# CH32V407VET-R0.net
KiCad netlist of a schematic drawn in Altium Designer
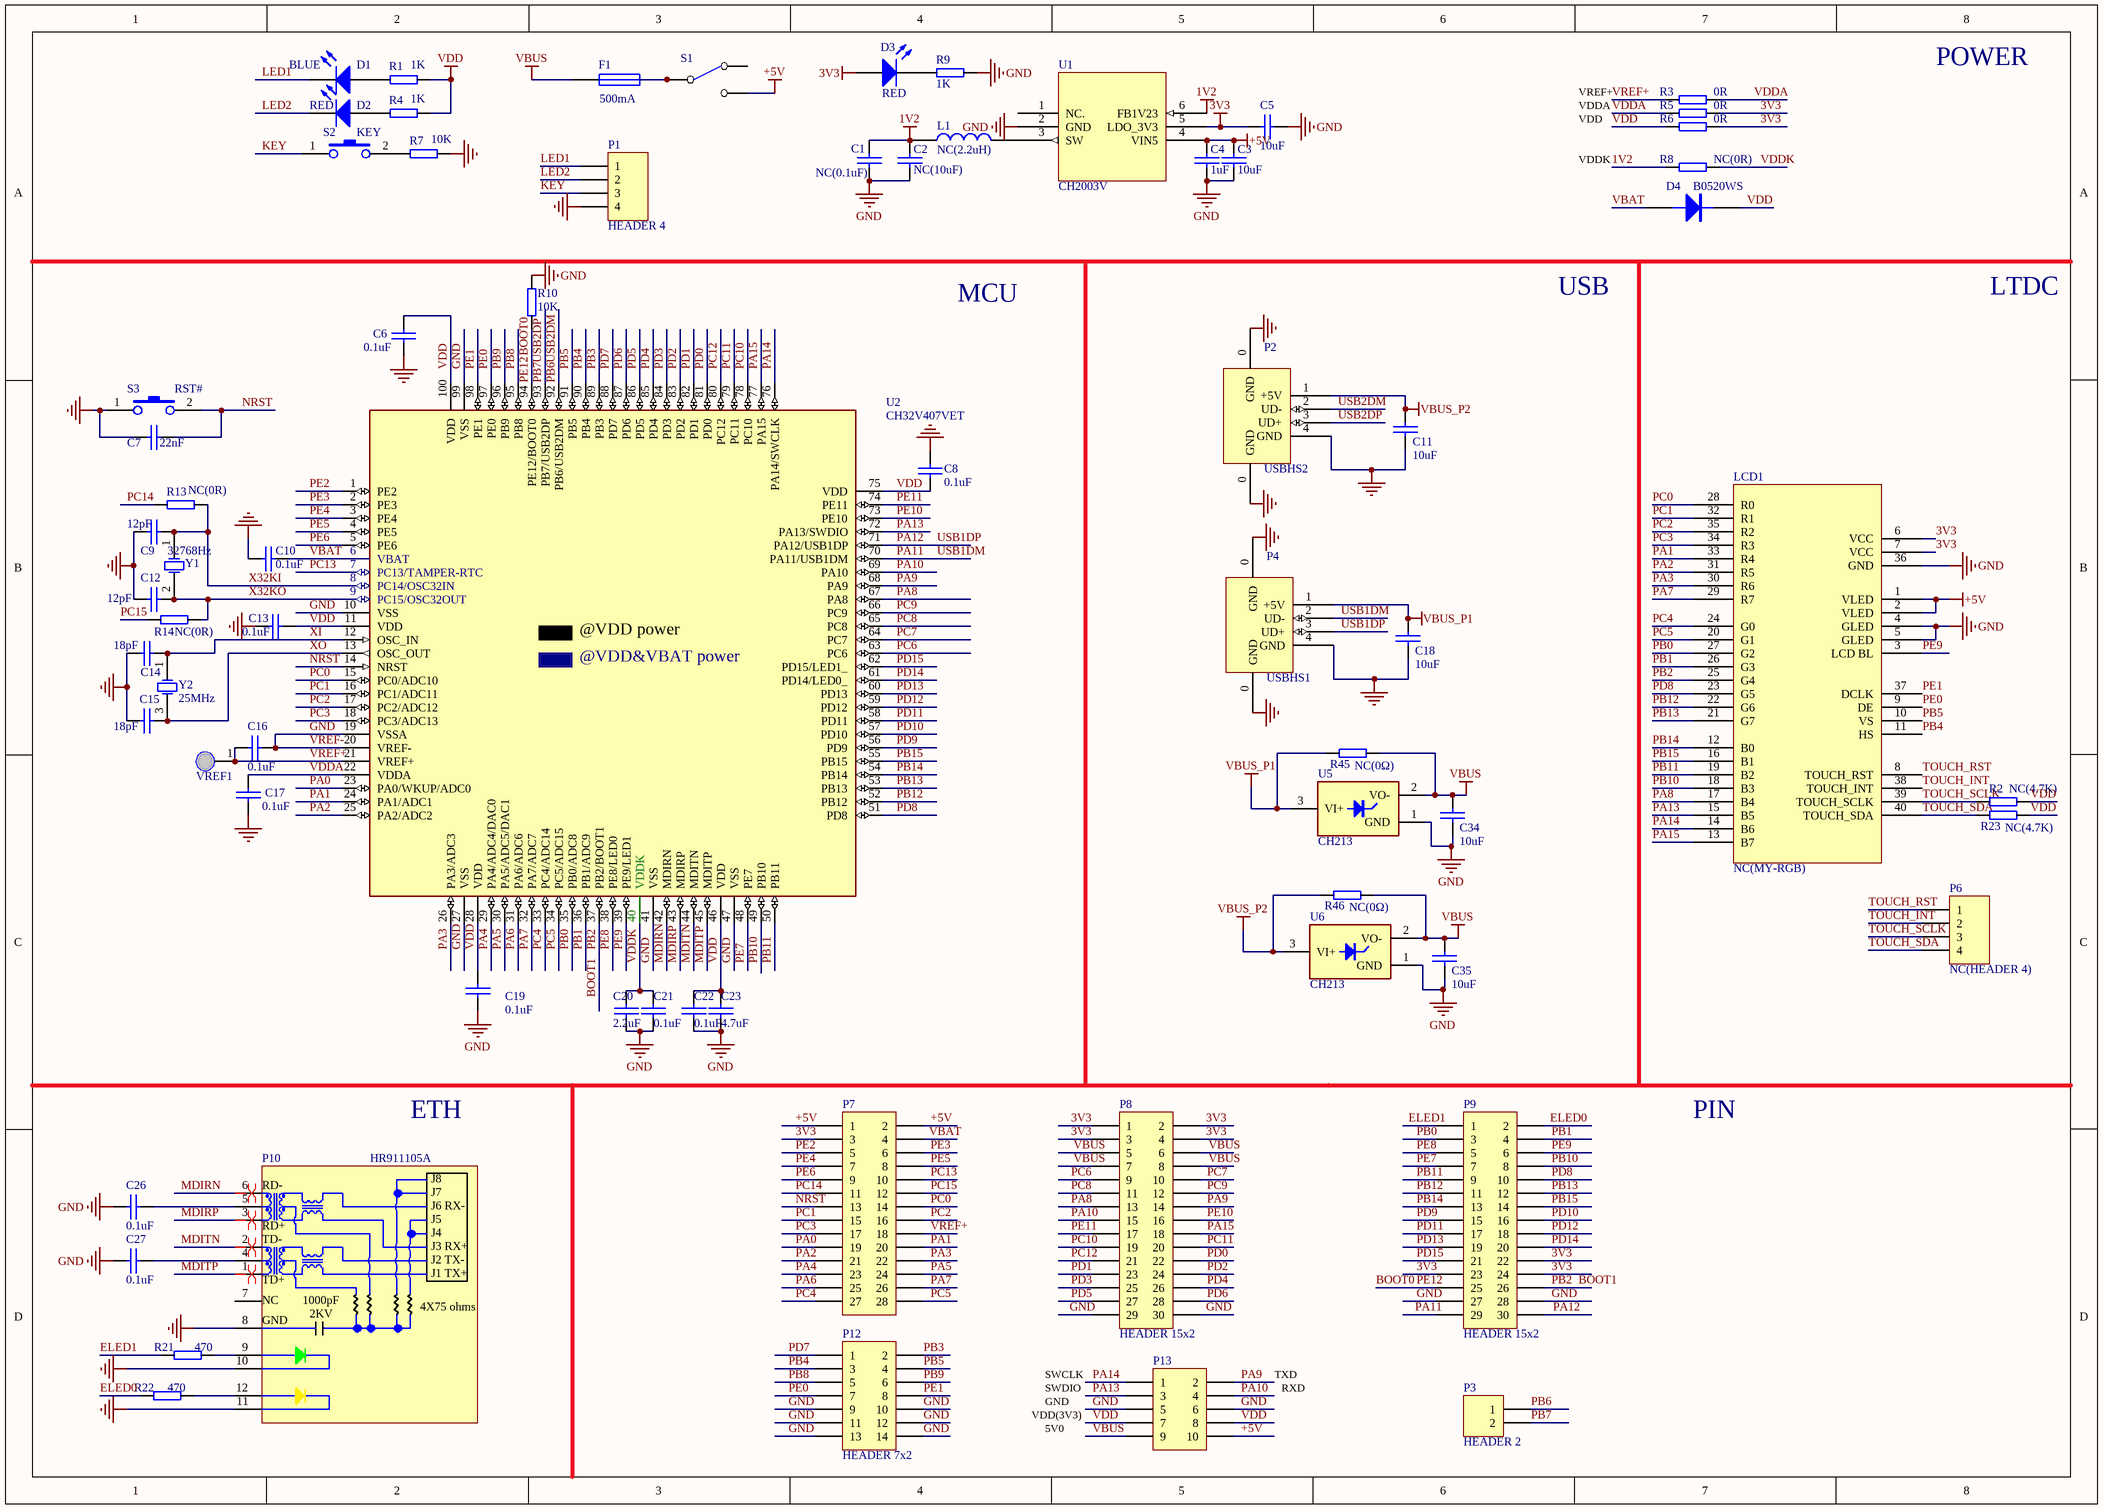
[diagram p0: CH32V407VET-R0.SchDoc]

(export (version "E")
  (design (tool "Eeschema 10.0.6"))
  (components
    (comp (ref "C1")
      (value "NC(0.1uF)")
      (footprint "0402_C")
      (description "Capacitor")
      (libsource (lib "") (part "CAP_1"))
    )
    (comp (ref "C2")
      (value "NC(10uF)")
      (footprint "0603_C")
      (description "Capacitor")
      (libsource (lib "*") (part "CAP"))
    )
    (comp (ref "C3")
      (value "10uF")
      (footprint "0603_C")
      (description "Capacitor")
      (libsource (lib "*") (part "CAP"))
    )
    (comp (ref "C4")
      (value "1uF")
      (footprint "0402_C")
      (description "Capacitor")
      (libsource (lib "") (part "CAP_1"))
    )
    (comp (ref "C5")
      (value "10uF")
      (footprint "0603_C")
      (description "Capacitor")
      (libsource (lib "*") (part "CAP"))
    )
    (comp (ref "C6")
      (value "0.1uF")
      (footprint "0402_C")
      (description "Capacitor")
      (libsource (lib "*") (part "CAP"))
    )
    (comp (ref "C7")
      (value "22nF")
      (footprint "0402_C")
      (description "Capacitor")
      (libsource (lib "") (part "CAP_2"))
    )
    (comp (ref "C8")
      (value "0.1uF")
      (footprint "0402_C")
      (description "Capacitor")
      (libsource (lib "*") (part "CAP"))
    )
    (comp (ref "C9")
      (value "12pF")
      (footprint "0402_C")
      (description "Capacitor")
      (libsource (lib "*") (part "CAP"))
    )
    (comp (ref "C10")
      (value "0.1uF")
      (footprint "0402_C")
      (description "Capacitor")
      (libsource (lib "*") (part "CAP"))
    )
    (comp (ref "C11")
      (value "10uF")
      (footprint "0603_C")
      (description "Capacitor")
      (libsource (lib "") (part "CAP_2"))
    )
    (comp (ref "C12")
      (value "12pF")
      (footprint "0402_C")
      (description "Capacitor")
      (libsource (lib "*") (part "CAP"))
    )
    (comp (ref "C13")
      (value "0.1uF")
      (footprint "0402_C")
      (description "Capacitor")
      (libsource (lib "*") (part "CAP"))
    )
    (comp (ref "C14")
      (value "18pF")
      (footprint "0402_C")
      (description "Capacitor")
      (libsource (lib "*") (part "CAP"))
    )
    (comp (ref "C15")
      (value "18pF")
      (footprint "0402_C")
      (description "Capacitor")
      (libsource (lib "*") (part "CAP"))
    )
    (comp (ref "C16")
      (value "0.1uF")
      (footprint "0402_C")
      (description "Capacitor")
      (libsource (lib "*") (part "CAP"))
    )
    (comp (ref "C17")
      (value "0.1uF")
      (footprint "0402_C")
      (description "Capacitor")
      (libsource (lib "*") (part "CAP"))
    )
    (comp (ref "C18")
      (value "10uF")
      (footprint "0603_C")
      (description "Capacitor")
      (libsource (lib "") (part "CAP_2"))
    )
    (comp (ref "C19")
      (value "0.1uF")
      (footprint "0402_C")
      (description "Capacitor")
      (libsource (lib "*") (part "CAP"))
    )
    (comp (ref "C20")
      (value "2.2uF")
      (footprint "0402_C")
      (description "Capacitor")
      (libsource (lib "*") (part "CAP"))
    )
    (comp (ref "C21")
      (value "0.1uF")
      (footprint "0402_C")
      (description "Capacitor")
      (libsource (lib "*") (part "CAP"))
    )
    (comp (ref "C22")
      (value "0.1uF")
      (footprint "0402_C")
      (description "Capacitor")
      (libsource (lib "*") (part "CAP"))
    )
    (comp (ref "C23")
      (value "4.7uF")
      (footprint "0402_C")
      (description "Capacitor")
      (libsource (lib "*") (part "CAP"))
    )
    (comp (ref "C26")
      (value "0.1uF")
      (footprint "0402_C")
      (description "Capacitor")
      (libsource (lib "wch_sch_others") (part "CAP"))
    )
    (comp (ref "C27")
      (value "0.1uF")
      (footprint "0402_C")
      (description "Capacitor")
      (libsource (lib "wch_sch_others") (part "CAP"))
    )
    (comp (ref "C34")
      (value "10uF")
      (footprint "0603_C")
      (description "Capacitor")
      (libsource (lib "") (part "CAP_2"))
    )
    (comp (ref "C35")
      (value "10uF")
      (footprint "0603_C")
      (description "Capacitor")
      (libsource (lib "") (part "CAP_2"))
    )
    (comp (ref "D1")
      (value "BLUE")
      (footprint "0603+")
      (description "Typical INFRARED GaAs LED")
      (fields (field (name "PUBLISHER") "Altium Limited"))
      (libsource (lib "*") (part "LED0"))
    )
    (comp (ref "D2")
      (value "RED")
      (footprint "0603+")
      (description "Typical INFRARED GaAs LED")
      (fields (field (name "PUBLISHER") "Altium Limited"))
      (libsource (lib "*") (part "LED0"))
    )
    (comp (ref "D3")
      (value "RED")
      (footprint "0603+")
      (description "Typical INFRARED GaAs LED")
      (fields (field (name "PUBLISHER") "Altium Limited"))
      (libsource (lib "*") (part "LED0"))
    )
    (comp (ref "D4")
      (value "B0520WS")
      (footprint "SOD-323")
      (description "Diode")
      (libsource (lib "*") (part "DIODE"))
    )
    (comp (ref "F1")
      (value "500mA")
      (footprint "0603")
      (description "Fuse")
      (libsource (lib "wch_sch_others") (part "FUSE1"))
    )
    (comp (ref "L1") (value "NC(2.2uH)") (footprint "CD32") (libsource (lib "*") (part "INDUCTOR")))
    (comp (ref "LCD1")
      (value "NC(MY-RGB)")
      (footprint "FPC40P-0.5-FK750M3")
      (libsource (lib "MY-显示") (part "MY-RGB"))
    )
    (comp (ref "P1")
      (value "HEADER 4")
      (footprint "SIP4-2.54mm")
      (description "Header, 4-Pin")
      (libsource (lib "wch_sch_others") (part "HEADER 4"))
    )
    (comp (ref "P2")
      (value "USBHS2")
      (footprint "USBAF")
      (description "USB Port")
      (libsource (lib "*") (part "USB"))
    )
    (comp (ref "P3")
      (value "HEADER 2")
      (footprint "MYPCB:SIP2-2.54mm")
      (description "Header, 2-Pin")
      (libsource (lib "wch_sch_others") (part "HEADER 2"))
    )
    (comp (ref "P4")
      (value "USBHS1")
      (footprint "USBAF")
      (description "USB Port")
      (libsource (lib "*") (part "USB"))
    )
    (comp (ref "P6")
      (value "NC(HEADER 4)")
      (footprint "SIP4-2.54mm")
      (description "Header, 4-Pin")
      (libsource (lib "wch_sch_others") (part "HEADER 4"))
    )
    (comp (ref "P7")
      (value "HEADER 14x2")
      (footprint "MYPCB:IDC28-2.54MM")
      (description "Header, 14-Pin, Dual row")
      (libsource (lib "wch_sch_others") (part "HEADER 14x2"))
    )
    (comp (ref "P8")
      (value "HEADER 15x2")
      (footprint "MYPCB:IDC30-2.54MM")
      (description "Header, 15-Pin, Dual row")
      (libsource (lib "wch_sch_others") (part "HEADER 15x2"))
    )
    (comp (ref "P9")
      (value "HEADER 15x2")
      (footprint "MYPCB:IDC30-2.54MM")
      (description "Header, 15-Pin, Dual row")
      (libsource (lib "wch_sch_others") (part "HEADER 15x2"))
    )
    (comp (ref "P10") (value "HR911105A") (footprint "HR911105A") (libsource (lib "*") (part "HR911105A")))
    (comp (ref "P12")
      (value "HEADER 7x2")
      (footprint "MYPCB:IDC14-2.54mm")
      (description "Header, 7-Pin, Dual row")
      (libsource (lib "wch_sch_others") (part "HEADER 7x2"))
    )
    (comp (ref "P13")
      (value "LINK")
      (footprint "IDC10-2.54mm")
      (description "Header, 5-Pin, Dual row, Right Angle")
      (fields (field (name "PUBLISHER") "Altium Limited"))
      (libsource (lib "Miscellaneous Connectors") (part "Header 5X2H"))
    )
    (comp (ref "R1") (value "1K") (footprint "0402") (libsource (lib "wch_sch_others") (part "RES")))
    (comp (ref "R2") (value "NC(4.7K)") (footprint "0402") (libsource (lib "wch_sch_others") (part "RES")))
    (comp (ref "R3") (value "0R") (footprint "0402") (libsource (lib "*") (part "R")))
    (comp (ref "R4") (value "1K") (footprint "0402") (libsource (lib "wch_sch_others") (part "RES")))
    (comp (ref "R5") (value "0R") (footprint "0402") (libsource (lib "*") (part "R")))
    (comp (ref "R6") (value "0R") (footprint "0402") (libsource (lib "*") (part "R")))
    (comp (ref "R7") (value "10K") (footprint "0402") (libsource (lib "wch_sch_others") (part "RES")))
    (comp (ref "R8") (value "NC(0R)") (footprint "0402") (libsource (lib "*") (part "R")))
    (comp (ref "R9") (value "1K") (footprint "0402") (libsource (lib "wch_sch_others") (part "RES")))
    (comp (ref "R10") (value "10K") (footprint "0402") (libsource (lib "wch_sch_others") (part "RES")))
    (comp (ref "R13") (value "NC(0R)") (footprint "0402") (libsource (lib "wch_sch_others") (part "RES")))
    (comp (ref "R14") (value "NC(0R)") (footprint "0402") (libsource (lib "wch_sch_others") (part "RES")))
    (comp (ref "R21") (value "470") (footprint "0402") (libsource (lib "wch_sch_others") (part "RES")))
    (comp (ref "R22") (value "470") (footprint "0402") (libsource (lib "wch_sch_others") (part "RES")))
    (comp (ref "R23") (value "NC(4.7K)") (footprint "0402") (libsource (lib "wch_sch_others") (part "RES")))
    (comp (ref "R45") (value "NC(0Ω)") (footprint "0402") (libsource (lib "wch_sch_others") (part "RES")))
    (comp (ref "R46") (value "NC(0Ω)") (footprint "0402") (libsource (lib "wch_sch_others") (part "RES")))
    (comp (ref "S1") (value "SW SPDT") (footprint "SW1") (libsource (lib "*") (part "SW SPDT")))
    (comp (ref "S2")
      (value "KEY")
      (footprint "SMD_6.1x3.65x2.5mm-KEY")
      (libsource (lib "wch_sch_others") (part "KEY1"))
    )
    (comp (ref "S3")
      (value "RST#")
      (footprint "SMD_6.1x3.65x2.5mm-KEY")
      (libsource (lib "wch_sch_others") (part "KEY1"))
    )
    (comp (ref "U1")
      (value "CH2003V")
      (footprint "SOT-23-6")
      (description "Step-Down DC-DC Converter, 5V input, 1.23V * 800mA output, with LDO 3.3V * 200mA")
      (libsource (lib "CHXXX") (part "CH2003V"))
    )
    (comp (ref "U2")
      (value "CH32V407VET")
      (footprint "LQFP100")
      (description "RISC-V FPU HD-MCU, 175MHz, USB_480M, 100M Ethernet & Phy, CAN, DVP, ADC, DAC")
      (libsource (lib "CHXXX") (part "CH32V407VET"))
    )
    (comp (ref "U5")
      (value "CH213")
      (footprint "SOT-23-3")
      (description "Ideal Diode 5V*1A")
      (libsource (lib "CHXXX") (part "CH213E"))
    )
    (comp (ref "U6")
      (value "CH213")
      (footprint "SOT-23-3")
      (description "Ideal Diode 5V*1A")
      (libsource (lib "CHXXX") (part "CH213E"))
    )
    (comp (ref "VREF1")
      (value "PAD")
      (footprint "TESTPOINT1")
      (description "焊盘")
      (libsource (lib "wch_sch_others") (part "PAD"))
    )
    (comp (ref "Y1")
      (value "32768Hz")
      (footprint "FC-135")
      (description "Crystal Oscillator")
      (fields (field (name "PUBLISHER") "Altium Limited"))
      (libsource (lib "") (part "XTAL_1"))
    )
    (comp (ref "Y2")
      (value "25MHz")
      (footprint "XT3225")
      (description "Crystal Oscillator")
      (fields (field (name "PUBLISHER") "Altium Limited"))
      (libsource (lib "*") (part "XTAL"))
    )
  )
  (nets
    (net (code "1") (name "+5V") (class "Default")
      (node (ref "C3") (pin "2") (pinfunction "2_2") (pintype "passive"))
      (node (ref "C4") (pin "2") (pinfunction "2_2") (pintype "passive"))
      (node (ref "LCD1") (pin "1") (pinfunction "VLED_1") (pintype "passive"))
      (node (ref "LCD1") (pin "2") (pinfunction "VLED_2") (pintype "passive"))
      (node (ref "P13") (pin "10") (pinfunction "10_10") (pintype "passive"))
      (node (ref "P7") (pin "1") (pinfunction "1_1") (pintype "passive"))
      (node (ref "P7") (pin "2") (pinfunction "2_2") (pintype "passive"))
      (node (ref "S1") (pin "2") (pinfunction "NC_2") (pintype "passive"))
      (node (ref "U1") (pin "4") (pinfunction "VIN5_4") (pintype "power_in"))
    )
    (net (code "3") (name "/BOOT0") (class "Default")
      (node (ref "P9") (pin "25") (pinfunction "25_25") (pintype "passive"))
      (node (ref "R10") (pin "2") (pintype "passive"))
      (node (ref "U2") (pin "94") (pinfunction "PE12/BOOT0_94") (pintype "bidirectional"))
    )
    (net (code "4") (name "/BOOT1") (class "Default")
      (node (ref "LCD1") (pin "25") (pinfunction "G4_25") (pintype "passive"))
      (node (ref "P9") (pin "26") (pinfunction "26_26") (pintype "passive"))
      (node (ref "U2") (pin "37") (pinfunction "PB2/BOOT1_37") (pintype "bidirectional"))
    )
    (net (code "5") (name "/ELED0") (class "Default")
      (node (ref "P9") (pin "2") (pinfunction "2_2") (pintype "passive"))
      (node (ref "R22") (pin "1") (pintype "passive"))
    )
    (net (code "6") (name "/ELED1") (class "Default")
      (node (ref "P9") (pin "1") (pinfunction "1_1") (pintype "passive"))
      (node (ref "R21") (pin "1") (pintype "passive"))
    )
    (net (code "7") (name "/KEY") (class "Default")
      (node (ref "P1") (pin "3") (pinfunction "3_3") (pintype "passive"))
      (node (ref "S2") (pin "1") (pinfunction "1_1") (pintype "passive"))
    )
    (net (code "8") (name "/LED1") (class "Default")
      (node (ref "D1") (pin "2") (pinfunction "K_2") (pintype "passive"))
      (node (ref "P1") (pin "1") (pinfunction "1_1") (pintype "passive"))
    )
    (net (code "9") (name "/LED2") (class "Default")
      (node (ref "D2") (pin "2") (pinfunction "K_2") (pintype "passive"))
      (node (ref "P1") (pin "2") (pinfunction "2_2") (pintype "passive"))
    )
    (net (code "10") (name "/MDIRN") (class "Default")
      (node (ref "P10") (pin "6") (pintype "passive"))
      (node (ref "U2") (pin "42") (pinfunction "MDIRN_42") (pintype "bidirectional"))
    )
    (net (code "11") (name "/MDIRP") (class "Default")
      (node (ref "P10") (pin "3") (pintype "passive"))
      (node (ref "U2") (pin "43") (pinfunction "MDIRP_43") (pintype "bidirectional"))
    )
    (net (code "12") (name "/MDITN") (class "Default")
      (node (ref "P10") (pin "2") (pintype "passive"))
      (node (ref "U2") (pin "44") (pinfunction "MDITN_44") (pintype "bidirectional"))
    )
    (net (code "13") (name "/MDITP") (class "Default")
      (node (ref "P10") (pin "1") (pintype "passive"))
      (node (ref "U2") (pin "45") (pinfunction "MDITP_45") (pintype "bidirectional"))
    )
    (net (code "14") (name "/NRST") (class "Default")
      (node (ref "C7") (pin "2") (pinfunction "2_2") (pintype "passive"))
      (node (ref "P7") (pin "13") (pinfunction "13_13") (pintype "passive"))
      (node (ref "S3") (pin "2") (pinfunction "2_2") (pintype "passive"))
      (node (ref "U2") (pin "14") (pinfunction "NRST_14") (pintype "input"))
    )
    (net (code "15") (name "/PA0") (class "Default")
      (node (ref "P7") (pin "19") (pinfunction "19_19") (pintype "passive"))
      (node (ref "U2") (pin "23") (pinfunction "PA0/WKUP/ADC0_23") (pintype "bidirectional"))
    )
    (net (code "16") (name "/PA1") (class "Default")
      (node (ref "LCD1") (pin "33") (pinfunction "R4_33") (pintype "passive"))
      (node (ref "P7") (pin "20") (pinfunction "20_20") (pintype "passive"))
      (node (ref "U2") (pin "24") (pinfunction "PA1/ADC1_24") (pintype "bidirectional"))
    )
    (net (code "17") (name "/PA2") (class "Default")
      (node (ref "LCD1") (pin "31") (pinfunction "R5_31") (pintype "passive"))
      (node (ref "P7") (pin "21") (pinfunction "21_21") (pintype "passive"))
      (node (ref "U2") (pin "25") (pinfunction "PA2/ADC2_25") (pintype "bidirectional"))
    )
    (net (code "18") (name "/PA3") (class "Default")
      (node (ref "LCD1") (pin "30") (pinfunction "R6_30") (pintype "passive"))
      (node (ref "P7") (pin "22") (pinfunction "22_22") (pintype "passive"))
      (node (ref "U2") (pin "26") (pinfunction "PA3/ADC3_26") (pintype "bidirectional"))
    )
    (net (code "19") (name "/PA4") (class "Default")
      (node (ref "P7") (pin "23") (pinfunction "23_23") (pintype "passive"))
      (node (ref "U2") (pin "29") (pinfunction "PA4/ADC4/DAC0_29") (pintype "bidirectional"))
    )
    (net (code "20") (name "/PA5") (class "Default")
      (node (ref "P7") (pin "24") (pinfunction "24_24") (pintype "passive"))
      (node (ref "U2") (pin "30") (pinfunction "PA5/ADC5/DAC1_30") (pintype "bidirectional"))
    )
    (net (code "21") (name "/PA6") (class "Default")
      (node (ref "P7") (pin "25") (pinfunction "25_25") (pintype "passive"))
      (node (ref "U2") (pin "31") (pinfunction "PA6/ADC6_31") (pintype "bidirectional"))
    )
    (net (code "22") (name "/PA7") (class "Default")
      (node (ref "LCD1") (pin "29") (pinfunction "R7_29") (pintype "passive"))
      (node (ref "P7") (pin "26") (pinfunction "26_26") (pintype "passive"))
      (node (ref "U2") (pin "32") (pinfunction "PA7/ADC7_32") (pintype "bidirectional"))
    )
    (net (code "23") (name "/PA8") (class "Default")
      (node (ref "LCD1") (pin "17") (pinfunction "B4_17") (pintype "passive"))
      (node (ref "P8") (pin "13") (pinfunction "13_13") (pintype "passive"))
      (node (ref "U2") (pin "67") (pinfunction "PA8_67") (pintype "bidirectional"))
    )
    (net (code "24") (name "/PA9") (class "Default")
      (node (ref "P13") (pin "2") (pinfunction "2_2") (pintype "passive"))
      (node (ref "P8") (pin "14") (pinfunction "14_14") (pintype "passive"))
      (node (ref "U2") (pin "68") (pinfunction "PA9_68") (pintype "bidirectional"))
    )
    (net (code "25") (name "/PA10") (class "Default")
      (node (ref "P13") (pin "4") (pinfunction "4_4") (pintype "passive"))
      (node (ref "P8") (pin "15") (pinfunction "15_15") (pintype "passive"))
      (node (ref "U2") (pin "69") (pinfunction "PA10_69") (pintype "bidirectional"))
    )
    (net (code "26") (name "/PA11") (class "Default")
      (node (ref "P4") (pin "2") (pinfunction "UD-_2") (pintype "bidirectional"))
      (node (ref "P9") (pin "29") (pinfunction "29_29") (pintype "passive"))
      (node (ref "U2") (pin "70") (pinfunction "PA11/USB1DM_70") (pintype "bidirectional"))
    )
    (net (code "27") (name "/PA12") (class "Default")
      (node (ref "P4") (pin "3") (pinfunction "UD+_3") (pintype "bidirectional"))
      (node (ref "P9") (pin "30") (pinfunction "30_30") (pintype "passive"))
      (node (ref "U2") (pin "71") (pinfunction "PA12/USB1DP_71") (pintype "bidirectional"))
    )
    (net (code "28") (name "/PA13") (class "Default")
      (node (ref "LCD1") (pin "15") (pinfunction "B5_15") (pintype "passive"))
      (node (ref "P13") (pin "3") (pinfunction "3_3") (pintype "passive"))
      (node (ref "U2") (pin "72") (pinfunction "PA13/SWDIO_72") (pintype "bidirectional"))
    )
    (net (code "29") (name "/PA14") (class "Default")
      (node (ref "LCD1") (pin "14") (pinfunction "B6_14") (pintype "passive"))
      (node (ref "P13") (pin "1") (pinfunction "1_1") (pintype "passive"))
      (node (ref "U2") (pin "76") (pinfunction "PA14/SWCLK_76") (pintype "bidirectional"))
    )
    (net (code "30") (name "/PA15") (class "Default")
      (node (ref "LCD1") (pin "13") (pinfunction "B7_13") (pintype "passive"))
      (node (ref "P8") (pin "18") (pinfunction "18_18") (pintype "passive"))
      (node (ref "U2") (pin "77") (pinfunction "PA15_77") (pintype "bidirectional"))
    )
    (net (code "31") (name "/PB0") (class "Default")
      (node (ref "LCD1") (pin "27") (pinfunction "G2_27") (pintype "passive"))
      (node (ref "P9") (pin "3") (pinfunction "3_3") (pintype "passive"))
      (node (ref "U2") (pin "35") (pinfunction "PB0/ADC8_35") (pintype "bidirectional"))
    )
    (net (code "32") (name "/PB1") (class "Default")
      (node (ref "LCD1") (pin "26") (pinfunction "G3_26") (pintype "passive"))
      (node (ref "P9") (pin "4") (pinfunction "4_4") (pintype "passive"))
      (node (ref "U2") (pin "36") (pinfunction "PB1/ADC9_36") (pintype "bidirectional"))
    )
    (net (code "33") (name "/PB3") (class "Default")
      (node (ref "P12") (pin "2") (pinfunction "2_2") (pintype "passive"))
      (node (ref "U2") (pin "89") (pinfunction "PB3_89") (pintype "bidirectional"))
    )
    (net (code "34") (name "/PB4") (class "Default")
      (node (ref "LCD1") (pin "11") (pinfunction "HS_11") (pintype "passive"))
      (node (ref "P12") (pin "3") (pinfunction "3_3") (pintype "passive"))
      (node (ref "U2") (pin "90") (pinfunction "PB4_90") (pintype "bidirectional"))
    )
    (net (code "35") (name "/PB5") (class "Default")
      (node (ref "LCD1") (pin "10") (pinfunction "VS_10") (pintype "passive"))
      (node (ref "P12") (pin "4") (pinfunction "4_4") (pintype "passive"))
      (node (ref "U2") (pin "91") (pinfunction "PB5_91") (pintype "bidirectional"))
    )
    (net (code "36") (name "/PB6") (class "Default")
      (node (ref "P2") (pin "2") (pinfunction "UD-_2") (pintype "bidirectional"))
      (node (ref "P3") (pin "1") (pinfunction "1_1") (pintype "passive"))
      (node (ref "U2") (pin "92") (pinfunction "PB6/USB2DM_92") (pintype "bidirectional"))
    )
    (net (code "37") (name "/PB7") (class "Default")
      (node (ref "P2") (pin "3") (pinfunction "UD+_3") (pintype "bidirectional"))
      (node (ref "P3") (pin "2") (pinfunction "2_2") (pintype "passive"))
      (node (ref "U2") (pin "93") (pinfunction "PB7/USB2DP_93") (pintype "bidirectional"))
    )
    (net (code "38") (name "/PB8") (class "Default")
      (node (ref "P12") (pin "5") (pinfunction "5_5") (pintype "passive"))
      (node (ref "U2") (pin "95") (pinfunction "PB8_95") (pintype "bidirectional"))
    )
    (net (code "39") (name "/PB9") (class "Default")
      (node (ref "P12") (pin "6") (pinfunction "6_6") (pintype "passive"))
      (node (ref "U2") (pin "96") (pinfunction "PB9_96") (pintype "bidirectional"))
    )
    (net (code "40") (name "/PB10") (class "Default")
      (node (ref "LCD1") (pin "18") (pinfunction "B3_18") (pintype "passive"))
      (node (ref "P9") (pin "8") (pinfunction "8_8") (pintype "passive"))
      (node (ref "U2") (pin "49") (pinfunction "PB10_49") (pintype "bidirectional"))
    )
    (net (code "41") (name "/PB11") (class "Default")
      (node (ref "LCD1") (pin "19") (pinfunction "B2_19") (pintype "passive"))
      (node (ref "P9") (pin "9") (pinfunction "9_9") (pintype "passive"))
      (node (ref "U2") (pin "50") (pinfunction "PB11_50") (pintype "bidirectional"))
    )
    (net (code "42") (name "/PB12") (class "Default")
      (node (ref "LCD1") (pin "22") (pinfunction "G6_22") (pintype "passive"))
      (node (ref "P9") (pin "11") (pinfunction "11_11") (pintype "passive"))
      (node (ref "U2") (pin "52") (pinfunction "PB12_52") (pintype "bidirectional"))
    )
    (net (code "43") (name "/PB13") (class "Default")
      (node (ref "LCD1") (pin "21") (pinfunction "G7_21") (pintype "passive"))
      (node (ref "P9") (pin "12") (pinfunction "12_12") (pintype "passive"))
      (node (ref "U2") (pin "53") (pinfunction "PB13_53") (pintype "bidirectional"))
    )
    (net (code "44") (name "/PB14") (class "Default")
      (node (ref "LCD1") (pin "12") (pinfunction "B0_12") (pintype "passive"))
      (node (ref "P9") (pin "13") (pinfunction "13_13") (pintype "passive"))
      (node (ref "U2") (pin "54") (pinfunction "PB14_54") (pintype "bidirectional"))
    )
    (net (code "45") (name "/PB15") (class "Default")
      (node (ref "LCD1") (pin "16") (pinfunction "B1_16") (pintype "passive"))
      (node (ref "P9") (pin "14") (pinfunction "14_14") (pintype "passive"))
      (node (ref "U2") (pin "55") (pinfunction "PB15_55") (pintype "bidirectional"))
    )
    (net (code "46") (name "/PC0") (class "Default")
      (node (ref "LCD1") (pin "28") (pinfunction "R0_28") (pintype "passive"))
      (node (ref "P7") (pin "14") (pinfunction "14_14") (pintype "passive"))
      (node (ref "U2") (pin "15") (pinfunction "PC0/ADC10_15") (pintype "bidirectional"))
    )
    (net (code "47") (name "/PC1") (class "Default")
      (node (ref "LCD1") (pin "32") (pinfunction "R1_32") (pintype "passive"))
      (node (ref "P7") (pin "15") (pinfunction "15_15") (pintype "passive"))
      (node (ref "U2") (pin "16") (pinfunction "PC1/ADC11_16") (pintype "bidirectional"))
    )
    (net (code "48") (name "/PC2") (class "Default")
      (node (ref "LCD1") (pin "35") (pinfunction "R2_35") (pintype "passive"))
      (node (ref "P7") (pin "16") (pinfunction "16_16") (pintype "passive"))
      (node (ref "U2") (pin "17") (pinfunction "PC2/ADC12_17") (pintype "bidirectional"))
    )
    (net (code "49") (name "/PC3") (class "Default")
      (node (ref "LCD1") (pin "34") (pinfunction "R3_34") (pintype "passive"))
      (node (ref "P7") (pin "17") (pinfunction "17_17") (pintype "passive"))
      (node (ref "U2") (pin "18") (pinfunction "PC3/ADC13_18") (pintype "bidirectional"))
    )
    (net (code "50") (name "/PC4") (class "Default")
      (node (ref "LCD1") (pin "24") (pinfunction "G0_24") (pintype "passive"))
      (node (ref "P7") (pin "27") (pinfunction "27_27") (pintype "passive"))
      (node (ref "U2") (pin "33") (pinfunction "PC4/ADC14_33") (pintype "bidirectional"))
    )
    (net (code "51") (name "/PC5") (class "Default")
      (node (ref "LCD1") (pin "20") (pinfunction "G1_20") (pintype "passive"))
      (node (ref "P7") (pin "28") (pinfunction "28_28") (pintype "passive"))
      (node (ref "U2") (pin "34") (pinfunction "PC5/ADC15_34") (pintype "bidirectional"))
    )
    (net (code "52") (name "/PC6") (class "Default")
      (node (ref "P8") (pin "9") (pinfunction "9_9") (pintype "passive"))
      (node (ref "U2") (pin "63") (pinfunction "PC6_63") (pintype "bidirectional"))
    )
    (net (code "53") (name "/PC7") (class "Default")
      (node (ref "P8") (pin "10") (pinfunction "10_10") (pintype "passive"))
      (node (ref "U2") (pin "64") (pinfunction "PC7_64") (pintype "bidirectional"))
    )
    (net (code "54") (name "/PC8") (class "Default")
      (node (ref "P8") (pin "11") (pinfunction "11_11") (pintype "passive"))
      (node (ref "U2") (pin "65") (pinfunction "PC8_65") (pintype "bidirectional"))
    )
    (net (code "55") (name "/PC9") (class "Default")
      (node (ref "P8") (pin "12") (pinfunction "12_12") (pintype "passive"))
      (node (ref "U2") (pin "66") (pinfunction "PC9_66") (pintype "bidirectional"))
    )
    (net (code "56") (name "/PC10") (class "Default")
      (node (ref "P8") (pin "19") (pinfunction "19_19") (pintype "passive"))
      (node (ref "U2") (pin "78") (pinfunction "PC10_78") (pintype "bidirectional"))
    )
    (net (code "57") (name "/PC11") (class "Default")
      (node (ref "P8") (pin "20") (pinfunction "20_20") (pintype "passive"))
      (node (ref "U2") (pin "79") (pinfunction "PC11_79") (pintype "bidirectional"))
    )
    (net (code "58") (name "/PC12") (class "Default")
      (node (ref "P8") (pin "21") (pinfunction "21_21") (pintype "passive"))
      (node (ref "U2") (pin "80") (pinfunction "PC12_80") (pintype "bidirectional"))
    )
    (net (code "59") (name "/PC13") (class "Default")
      (node (ref "P7") (pin "10") (pinfunction "10_10") (pintype "passive"))
      (node (ref "U2") (pin "7") (pinfunction "PC13/TAMPER-RTC_7") (pintype "bidirectional"))
    )
    (net (code "60") (name "/PC14") (class "Default")
      (node (ref "P7") (pin "11") (pinfunction "11_11") (pintype "passive"))
      (node (ref "R13") (pin "1") (pintype "passive"))
    )
    (net (code "61") (name "/PC15") (class "Default")
      (node (ref "P7") (pin "12") (pinfunction "12_12") (pintype "passive"))
      (node (ref "R14") (pin "1") (pintype "passive"))
    )
    (net (code "62") (name "/PD0") (class "Default")
      (node (ref "P8") (pin "22") (pinfunction "22_22") (pintype "passive"))
      (node (ref "U2") (pin "81") (pinfunction "PD0_81") (pintype "bidirectional"))
    )
    (net (code "63") (name "/PD1") (class "Default")
      (node (ref "P8") (pin "23") (pinfunction "23_23") (pintype "passive"))
      (node (ref "U2") (pin "82") (pinfunction "PD1_82") (pintype "bidirectional"))
    )
    (net (code "64") (name "/PD2") (class "Default")
      (node (ref "P8") (pin "24") (pinfunction "24_24") (pintype "passive"))
      (node (ref "U2") (pin "83") (pinfunction "PD2_83") (pintype "bidirectional"))
    )
    (net (code "65") (name "/PD3") (class "Default")
      (node (ref "P8") (pin "25") (pinfunction "25_25") (pintype "passive"))
      (node (ref "U2") (pin "84") (pinfunction "PD3_84") (pintype "bidirectional"))
    )
    (net (code "66") (name "/PD4") (class "Default")
      (node (ref "P8") (pin "26") (pinfunction "26_26") (pintype "passive"))
      (node (ref "U2") (pin "85") (pinfunction "PD4_85") (pintype "bidirectional"))
    )
    (net (code "67") (name "/PD5") (class "Default")
      (node (ref "P8") (pin "27") (pinfunction "27_27") (pintype "passive"))
      (node (ref "U2") (pin "86") (pinfunction "PD5_86") (pintype "bidirectional"))
    )
    (net (code "68") (name "/PD6") (class "Default")
      (node (ref "P8") (pin "28") (pinfunction "28_28") (pintype "passive"))
      (node (ref "U2") (pin "87") (pinfunction "PD6_87") (pintype "bidirectional"))
    )
    (net (code "69") (name "/PD7") (class "Default")
      (node (ref "P12") (pin "1") (pinfunction "1_1") (pintype "passive"))
      (node (ref "U2") (pin "88") (pinfunction "PD7_88") (pintype "bidirectional"))
    )
    (net (code "70") (name "/PD8") (class "Default")
      (node (ref "LCD1") (pin "23") (pinfunction "G5_23") (pintype "passive"))
      (node (ref "P9") (pin "10") (pinfunction "10_10") (pintype "passive"))
      (node (ref "U2") (pin "51") (pinfunction "PD8_51") (pintype "bidirectional"))
    )
    (net (code "71") (name "/PD9") (class "Default")
      (node (ref "P9") (pin "15") (pinfunction "15_15") (pintype "passive"))
      (node (ref "U2") (pin "56") (pinfunction "PD9_56") (pintype "bidirectional"))
    )
    (net (code "72") (name "/PD10") (class "Default")
      (node (ref "P9") (pin "16") (pinfunction "16_16") (pintype "passive"))
      (node (ref "U2") (pin "57") (pinfunction "PD10_57") (pintype "bidirectional"))
    )
    (net (code "73") (name "/PD11") (class "Default")
      (node (ref "P9") (pin "17") (pinfunction "17_17") (pintype "passive"))
      (node (ref "U2") (pin "58") (pinfunction "PD11_58") (pintype "bidirectional"))
    )
    (net (code "74") (name "/PD12") (class "Default")
      (node (ref "P9") (pin "18") (pinfunction "18_18") (pintype "passive"))
      (node (ref "U2") (pin "59") (pinfunction "PD12_59") (pintype "bidirectional"))
    )
    (net (code "75") (name "/PD13") (class "Default")
      (node (ref "P9") (pin "19") (pinfunction "19_19") (pintype "passive"))
      (node (ref "U2") (pin "60") (pinfunction "PD13_60") (pintype "bidirectional"))
    )
    (net (code "76") (name "/PD14") (class "Default")
      (node (ref "P9") (pin "20") (pinfunction "20_20") (pintype "passive"))
      (node (ref "U2") (pin "61") (pinfunction "PD14/LED0__61") (pintype "bidirectional"))
    )
    (net (code "77") (name "/PD15") (class "Default")
      (node (ref "P9") (pin "21") (pinfunction "21_21") (pintype "passive"))
      (node (ref "U2") (pin "62") (pinfunction "PD15/LED1__62") (pintype "bidirectional"))
    )
    (net (code "78") (name "/PE0") (class "Default")
      (node (ref "LCD1") (pin "9") (pinfunction "DE_9") (pintype "passive"))
      (node (ref "P12") (pin "7") (pinfunction "7_7") (pintype "passive"))
      (node (ref "U2") (pin "97") (pinfunction "PE0_97") (pintype "bidirectional"))
    )
    (net (code "79") (name "/PE1") (class "Default")
      (node (ref "LCD1") (pin "37") (pinfunction "DCLK_37") (pintype "passive"))
      (node (ref "P12") (pin "8") (pinfunction "8_8") (pintype "passive"))
      (node (ref "U2") (pin "98") (pinfunction "PE1_98") (pintype "bidirectional"))
    )
    (net (code "80") (name "/PE2") (class "Default")
      (node (ref "P7") (pin "5") (pinfunction "5_5") (pintype "passive"))
      (node (ref "U2") (pin "1") (pinfunction "PE2_1") (pintype "bidirectional"))
    )
    (net (code "81") (name "/PE3") (class "Default")
      (node (ref "P7") (pin "6") (pinfunction "6_6") (pintype "passive"))
      (node (ref "U2") (pin "2") (pinfunction "PE3_2") (pintype "bidirectional"))
    )
    (net (code "82") (name "/PE4") (class "Default")
      (node (ref "P7") (pin "7") (pinfunction "7_7") (pintype "passive"))
      (node (ref "U2") (pin "3") (pinfunction "PE4_3") (pintype "bidirectional"))
    )
    (net (code "83") (name "/PE5") (class "Default")
      (node (ref "P7") (pin "8") (pinfunction "8_8") (pintype "passive"))
      (node (ref "U2") (pin "4") (pinfunction "PE5_4") (pintype "bidirectional"))
    )
    (net (code "84") (name "/PE6") (class "Default")
      (node (ref "P7") (pin "9") (pinfunction "9_9") (pintype "passive"))
      (node (ref "U2") (pin "5") (pinfunction "PE6_5") (pintype "bidirectional"))
    )
    (net (code "85") (name "/PE7") (class "Default")
      (node (ref "P9") (pin "7") (pinfunction "7_7") (pintype "passive"))
      (node (ref "U2") (pin "48") (pinfunction "PE7_48") (pintype "bidirectional"))
    )
    (net (code "86") (name "/PE8") (class "Default")
      (node (ref "P9") (pin "5") (pinfunction "5_5") (pintype "passive"))
      (node (ref "U2") (pin "38") (pinfunction "PE8/LED0_38") (pintype "bidirectional"))
    )
    (net (code "87") (name "/PE9") (class "Default")
      (node (ref "LCD1") (pin "3") (pinfunction "LCD_BL_3") (pintype "passive"))
      (node (ref "P9") (pin "6") (pinfunction "6_6") (pintype "passive"))
      (node (ref "U2") (pin "39") (pinfunction "PE9/LED1_39") (pintype "bidirectional"))
    )
    (net (code "88") (name "/PE10") (class "Default")
      (node (ref "P8") (pin "16") (pinfunction "16_16") (pintype "passive"))
      (node (ref "U2") (pin "73") (pinfunction "PE10_73") (pintype "bidirectional"))
    )
    (net (code "89") (name "/PE11") (class "Default")
      (node (ref "P8") (pin "17") (pinfunction "17_17") (pintype "passive"))
      (node (ref "U2") (pin "74") (pinfunction "PE11_74") (pintype "bidirectional"))
    )
    (net (code "90") (name "/TOUCH_INT") (class "Default")
      (node (ref "LCD1") (pin "38") (pinfunction "TOUCH_INT_38") (pintype "passive"))
      (node (ref "P6") (pin "2") (pinfunction "2_2") (pintype "passive"))
    )
    (net (code "91") (name "/TOUCH_RST") (class "Default")
      (node (ref "LCD1") (pin "8") (pinfunction "TOUCH_RST_8") (pintype "passive"))
      (node (ref "P6") (pin "1") (pinfunction "1_1") (pintype "passive"))
    )
    (net (code "92") (name "/TOUCH_SCLK") (class "Default")
      (node (ref "LCD1") (pin "39") (pinfunction "TOUCH_SCLK_39") (pintype "passive"))
      (node (ref "P6") (pin "3") (pinfunction "3_3") (pintype "passive"))
      (node (ref "R2") (pin "2") (pintype "passive"))
    )
    (net (code "93") (name "/TOUCH_SDA") (class "Default")
      (node (ref "LCD1") (pin "40") (pinfunction "TOUCH_SDA_40") (pintype "passive"))
      (node (ref "P6") (pin "4") (pinfunction "4_4") (pintype "passive"))
      (node (ref "R23") (pin "2") (pintype "passive"))
    )
    (net (code "94") (name "/VBAT") (class "Default")
      (node (ref "C10") (pin "2") (pinfunction "2_2") (pintype "passive"))
      (node (ref "D4") (pin "1") (pinfunction "A_1") (pintype "passive"))
      (node (ref "P7") (pin "4") (pinfunction "4_4") (pintype "passive"))
      (node (ref "U2") (pin "6") (pinfunction "VBAT_6") (pintype "power_in"))
    )
    (net (code "95") (name "/VDDA") (class "Default")
      (node (ref "C17") (pin "1") (pinfunction "1_1") (pintype "passive"))
      (node (ref "R3") (pin "1") (pinfunction "1_1") (pintype "passive"))
      (node (ref "R5") (pin "2") (pinfunction "2_2") (pintype "passive"))
      (node (ref "U2") (pin "22") (pinfunction "VDDA_22") (pintype "power_in"))
    )
    (net (code "96") (name "/VDDK") (class "Default")
      (node (ref "C20") (pin "2") (pinfunction "2_2") (pintype "passive"))
      (node (ref "C21") (pin "2") (pinfunction "2_2") (pintype "passive"))
      (node (ref "R8") (pin "1") (pinfunction "1_1") (pintype "passive"))
      (node (ref "U2") (pin "40") (pinfunction "VDDK_40") (pintype "power_in"))
    )
    (net (code "97") (name "/VREF+") (class "Default")
      (node (ref "C16") (pin "1") (pinfunction "1_1") (pintype "passive"))
      (node (ref "P7") (pin "18") (pinfunction "18_18") (pintype "passive"))
      (node (ref "R3") (pin "2") (pinfunction "2_2") (pintype "passive"))
      (node (ref "U2") (pin "21") (pinfunction "VREF+_21") (pintype "power_in"))
      (node (ref "VREF1") (pin "1") (pintype "passive"))
    )
    (net (code "98") (name "/X32KI") (class "Default")
      (node (ref "C9") (pin "2") (pinfunction "2_2") (pintype "passive"))
      (node (ref "R13") (pin "2") (pintype "passive"))
      (node (ref "U2") (pin "8") (pinfunction "PC14/OSC32IN_8") (pintype "bidirectional"))
      (node (ref "Y1") (pin "1") (pinfunction "OSC1_1") (pintype "passive"))
    )
    (net (code "99") (name "/X32KO") (class "Default")
      (node (ref "C12") (pin "2") (pinfunction "2_2") (pintype "passive"))
      (node (ref "R14") (pin "2") (pintype "passive"))
      (node (ref "U2") (pin "9") (pinfunction "PC15/OSC32OUT_9") (pintype "bidirectional"))
      (node (ref "Y1") (pin "2") (pinfunction "OSC2_2") (pintype "passive"))
    )
    (net (code "100") (name "/XI") (class "Default")
      (node (ref "C14") (pin "2") (pinfunction "2_2") (pintype "passive"))
      (node (ref "U2") (pin "12") (pinfunction "OSC_IN_12") (pintype "input"))
      (node (ref "Y2") (pin "1") (pinfunction "OSC1_1") (pintype "passive"))
    )
    (net (code "101") (name "/XO") (class "Default")
      (node (ref "C15") (pin "2") (pinfunction "2_2") (pintype "passive"))
      (node (ref "U2") (pin "13") (pinfunction "OSC_OUT_13") (pintype "output"))
      (node (ref "Y2") (pin "3") (pinfunction "OSC2_3") (pintype "passive"))
    )
    (net (code "102") (name "1V2") (class "Default")
      (node (ref "C1") (pin "2") (pinfunction "2_2") (pintype "passive"))
      (node (ref "C2") (pin "2") (pinfunction "2_2") (pintype "passive"))
      (node (ref "L1") (pin "2") (pinfunction "2_2") (pintype "passive"))
      (node (ref "R8") (pin "2") (pinfunction "2_2") (pintype "passive"))
      (node (ref "U1") (pin "6") (pinfunction "FB1V23_6") (pintype "input"))
    )
    (net (code "103") (name "3V3") (class "Default")
      (node (ref "C5") (pin "2") (pinfunction "2_2") (pintype "passive"))
      (node (ref "D3") (pin "1") (pinfunction "A_1") (pintype "passive"))
      (node (ref "LCD1") (pin "6") (pinfunction "VCC_6") (pintype "passive"))
      (node (ref "LCD1") (pin "7") (pinfunction "VCC_7") (pintype "passive"))
      (node (ref "P7") (pin "3") (pinfunction "3_3") (pintype "passive"))
      (node (ref "P8") (pin "1") (pinfunction "1_1") (pintype "passive"))
      (node (ref "P8") (pin "2") (pinfunction "2_2") (pintype "passive"))
      (node (ref "P8") (pin "3") (pinfunction "3_3") (pintype "passive"))
      (node (ref "P8") (pin "4") (pinfunction "4_4") (pintype "passive"))
      (node (ref "P9") (pin "22") (pinfunction "22_22") (pintype "passive"))
      (node (ref "P9") (pin "23") (pinfunction "23_23") (pintype "passive"))
      (node (ref "P9") (pin "24") (pinfunction "24_24") (pintype "passive"))
      (node (ref "R5") (pin "1") (pinfunction "1_1") (pintype "passive"))
      (node (ref "R6") (pin "1") (pinfunction "1_1") (pintype "passive"))
      (node (ref "U1") (pin "5") (pinfunction "LDO_3V3_5") (pintype "power_in"))
    )
    (net (code "104") (name "GND") (class "Default")
      (node (ref "C1") (pin "1") (pinfunction "1_1") (pintype "passive"))
      (node (ref "C10") (pin "1") (pinfunction "1_1") (pintype "passive"))
      (node (ref "C11") (pin "2") (pinfunction "2_2") (pintype "passive"))
      (node (ref "C12") (pin "1") (pinfunction "1_1") (pintype "passive"))
      (node (ref "C13") (pin "2") (pinfunction "2_2") (pintype "passive"))
      (node (ref "C14") (pin "1") (pinfunction "1_1") (pintype "passive"))
      (node (ref "C15") (pin "1") (pinfunction "1_1") (pintype "passive"))
      (node (ref "C16") (pin "2") (pinfunction "2_2") (pintype "passive"))
      (node (ref "C17") (pin "2") (pinfunction "2_2") (pintype "passive"))
      (node (ref "C18") (pin "2") (pinfunction "2_2") (pintype "passive"))
      (node (ref "C19") (pin "1") (pinfunction "1_1") (pintype "passive"))
      (node (ref "C2") (pin "1") (pinfunction "1_1") (pintype "passive"))
      (node (ref "C20") (pin "1") (pinfunction "1_1") (pintype "passive"))
      (node (ref "C21") (pin "1") (pinfunction "1_1") (pintype "passive"))
      (node (ref "C22") (pin "1") (pinfunction "1_1") (pintype "passive"))
      (node (ref "C23") (pin "1") (pinfunction "1_1") (pintype "passive"))
      (node (ref "C26") (pin "1") (pinfunction "1_1") (pintype "passive"))
      (node (ref "C27") (pin "1") (pinfunction "1_1") (pintype "passive"))
      (node (ref "C3") (pin "1") (pinfunction "1_1") (pintype "passive"))
      (node (ref "C34") (pin "2") (pinfunction "2_2") (pintype "passive"))
      (node (ref "C35") (pin "2") (pinfunction "2_2") (pintype "passive"))
      (node (ref "C4") (pin "1") (pinfunction "1_1") (pintype "passive"))
      (node (ref "C5") (pin "1") (pinfunction "1_1") (pintype "passive"))
      (node (ref "C6") (pin "1") (pinfunction "1_1") (pintype "passive"))
      (node (ref "C7") (pin "1") (pinfunction "1_1") (pintype "passive"))
      (node (ref "C8") (pin "2") (pinfunction "2_2") (pintype "passive"))
      (node (ref "C9") (pin "1") (pinfunction "1_1") (pintype "passive"))
      (node (ref "LCD1") (pin "36") (pinfunction "GND_36") (pintype "passive"))
      (node (ref "LCD1") (pin "4") (pinfunction "GLED_4") (pintype "passive"))
      (node (ref "LCD1") (pin "5") (pinfunction "GLED_5") (pintype "passive"))
      (node (ref "P1") (pin "4") (pinfunction "4_4") (pintype "passive"))
      (node (ref "P10") (pin "10") (pintype "passive"))
      (node (ref "P10") (pin "11") (pintype "passive"))
      (node (ref "P10") (pin "8") (pintype "passive"))
      (node (ref "P12") (pin "10") (pinfunction "10_10") (pintype "passive"))
      (node (ref "P12") (pin "11") (pinfunction "11_11") (pintype "passive"))
      (node (ref "P12") (pin "12") (pinfunction "12_12") (pintype "passive"))
      (node (ref "P12") (pin "13") (pinfunction "13_13") (pintype "passive"))
      (node (ref "P12") (pin "14") (pinfunction "14_14") (pintype "passive"))
      (node (ref "P12") (pin "9") (pinfunction "9_9") (pintype "passive"))
      (node (ref "P13") (pin "5") (pinfunction "5_5") (pintype "passive"))
      (node (ref "P13") (pin "6") (pinfunction "6_6") (pintype "passive"))
      (node (ref "P2") (pin "0") (pinfunction "GND_0") (pintype "power_in"))
      (node (ref "P2") (pin "4") (pinfunction "GND_4") (pintype "power_in"))
      (node (ref "P4") (pin "0") (pinfunction "GND_0") (pintype "power_in"))
      (node (ref "P4") (pin "4") (pinfunction "GND_4") (pintype "power_in"))
      (node (ref "P8") (pin "29") (pinfunction "29_29") (pintype "passive"))
      (node (ref "P8") (pin "30") (pinfunction "30_30") (pintype "passive"))
      (node (ref "P9") (pin "27") (pinfunction "27_27") (pintype "passive"))
      (node (ref "P9") (pin "28") (pinfunction "28_28") (pintype "passive"))
      (node (ref "R10") (pin "1") (pintype "passive"))
      (node (ref "R7") (pin "1") (pintype "passive"))
      (node (ref "R9") (pin "2") (pintype "passive"))
      (node (ref "S3") (pin "1") (pinfunction "1_1") (pintype "passive"))
      (node (ref "U1") (pin "2") (pinfunction "GND_2") (pintype "power_in"))
      (node (ref "U2") (pin "10") (pinfunction "VSS_10") (pintype "power_in"))
      (node (ref "U2") (pin "19") (pinfunction "VSSA_19") (pintype "power_in"))
      (node (ref "U2") (pin "20") (pinfunction "VREF-_20") (pintype "power_in"))
      (node (ref "U2") (pin "27") (pinfunction "VSS_27") (pintype "power_in"))
      (node (ref "U2") (pin "41") (pinfunction "VSS_41") (pintype "power_in"))
      (node (ref "U2") (pin "47") (pinfunction "VSS_47") (pintype "power_in"))
      (node (ref "U2") (pin "99") (pinfunction "VSS_99") (pintype "power_in"))
      (node (ref "U5") (pin "1") (pinfunction "GND_1") (pintype "power_in"))
      (node (ref "U6") (pin "1") (pinfunction "GND_1") (pintype "power_in"))
    )
    (net (code "105") (name "Net-(C26-Pad2)") (class "Default")
      (node (ref "C26") (pin "2") (pinfunction "2_2") (pintype "passive"))
      (node (ref "P10") (pin "5") (pintype "passive"))
    )
    (net (code "106") (name "Net-(C27-Pad2)") (class "Default")
      (node (ref "C27") (pin "2") (pinfunction "2_2") (pintype "passive"))
      (node (ref "P10") (pin "4") (pintype "passive"))
    )
    (net (code "107") (name "Net-(D1-A)") (class "Default")
      (node (ref "D1") (pin "1") (pinfunction "A_1") (pintype "passive"))
      (node (ref "R1") (pin "2") (pintype "passive"))
    )
    (net (code "108") (name "Net-(D2-A)") (class "Default")
      (node (ref "D2") (pin "1") (pinfunction "A_1") (pintype "passive"))
      (node (ref "R4") (pin "2") (pintype "passive"))
    )
    (net (code "109") (name "Net-(D3-K)") (class "Default")
      (node (ref "D3") (pin "2") (pinfunction "K_2") (pintype "passive"))
      (node (ref "R9") (pin "1") (pintype "passive"))
    )
    (net (code "110") (name "Net-(P10-Pad9)") (class "Default")
      (node (ref "P10") (pin "9") (pintype "passive"))
      (node (ref "R21") (pin "2") (pintype "passive"))
    )
    (net (code "111") (name "Net-(P10-Pad12)") (class "Default")
      (node (ref "P10") (pin "12") (pintype "passive"))
      (node (ref "R22") (pin "2") (pintype "passive"))
    )
    (net (code "112") (name "Net-(R7-Pad2)") (class "Default")
      (node (ref "R7") (pin "2") (pintype "passive"))
      (node (ref "S2") (pin "2") (pinfunction "2_2") (pintype "passive"))
    )
    (net (code "113") (name "Net-(S1-COMMON)") (class "Default")
      (node (ref "F1") (pin "2") (pinfunction "2_2") (pintype "passive"))
      (node (ref "S1") (pin "1") (pinfunction "COMMON_1") (pintype "passive"))
    )
    (net (code "114") (name "Net-(U1-SW)") (class "Default")
      (node (ref "L1") (pin "1") (pinfunction "1_1") (pintype "passive"))
      (node (ref "U1") (pin "3") (pinfunction "SW_3") (pintype "output"))
    )
    (net (code "115") (name "VBUS") (class "Default")
      (node (ref "C34") (pin "1") (pinfunction "1_1") (pintype "passive"))
      (node (ref "C35") (pin "1") (pinfunction "1_1") (pintype "passive"))
      (node (ref "F1") (pin "1") (pinfunction "1_1") (pintype "passive"))
      (node (ref "P13") (pin "9") (pinfunction "9_9") (pintype "passive"))
      (node (ref "P8") (pin "5") (pinfunction "5_5") (pintype "passive"))
      (node (ref "P8") (pin "6") (pinfunction "6_6") (pintype "passive"))
      (node (ref "P8") (pin "7") (pinfunction "7_7") (pintype "passive"))
      (node (ref "P8") (pin "8") (pinfunction "8_8") (pintype "passive"))
      (node (ref "R45") (pin "1") (pintype "passive"))
      (node (ref "R46") (pin "1") (pintype "passive"))
      (node (ref "U5") (pin "2") (pinfunction "VO-_2") (pintype "power_in"))
      (node (ref "U6") (pin "2") (pinfunction "VO-_2") (pintype "power_in"))
    )
    (net (code "116") (name "VBUS_P1") (class "Default")
      (node (ref "C18") (pin "1") (pinfunction "1_1") (pintype "passive"))
      (node (ref "P4") (pin "1") (pinfunction "+5V_1") (pintype "power_in"))
      (node (ref "R45") (pin "2") (pintype "passive"))
      (node (ref "U5") (pin "3") (pinfunction "VI+_3") (pintype "power_in"))
    )
    (net (code "117") (name "VBUS_P2") (class "Default")
      (node (ref "C11") (pin "1") (pinfunction "1_1") (pintype "passive"))
      (node (ref "P2") (pin "1") (pinfunction "+5V_1") (pintype "power_in"))
      (node (ref "R46") (pin "2") (pintype "passive"))
      (node (ref "U6") (pin "3") (pinfunction "VI+_3") (pintype "power_in"))
    )
    (net (code "118") (name "VDD") (class "Default")
      (node (ref "C13") (pin "1") (pinfunction "1_1") (pintype "passive"))
      (node (ref "C19") (pin "2") (pinfunction "2_2") (pintype "passive"))
      (node (ref "C22") (pin "2") (pinfunction "2_2") (pintype "passive"))
      (node (ref "C23") (pin "2") (pinfunction "2_2") (pintype "passive"))
      (node (ref "C6") (pin "2") (pinfunction "2_2") (pintype "passive"))
      (node (ref "C8") (pin "1") (pinfunction "1_1") (pintype "passive"))
      (node (ref "D4") (pin "2") (pinfunction "K_2") (pintype "passive"))
      (node (ref "P13") (pin "7") (pinfunction "7_7") (pintype "passive"))
      (node (ref "P13") (pin "8") (pinfunction "8_8") (pintype "passive"))
      (node (ref "R1") (pin "1") (pintype "passive"))
      (node (ref "R2") (pin "1") (pintype "passive"))
      (node (ref "R23") (pin "1") (pintype "passive"))
      (node (ref "R4") (pin "1") (pintype "passive"))
      (node (ref "R6") (pin "2") (pinfunction "2_2") (pintype "passive"))
      (node (ref "U2") (pin "100") (pinfunction "VDD_100") (pintype "power_in"))
      (node (ref "U2") (pin "11") (pinfunction "VDD_11") (pintype "power_in"))
      (node (ref "U2") (pin "28") (pinfunction "VDD_28") (pintype "power_in"))
      (node (ref "U2") (pin "46") (pinfunction "VDD_46") (pintype "power_in"))
      (node (ref "U2") (pin "75") (pinfunction "VDD_75") (pintype "power_in"))
    )
    (net (code "119") (name "unconnected-(P10-Pad7)") (class "Default")
      (node (ref "P10") (pin "7") (pintype "passive"))
    )
    (net (code "120") (name "unconnected-(S1-NO-Pad3)") (class "Default")
      (node (ref "S1") (pin "3") (pinfunction "NO_3") (pintype "passive"))
    )
    (net (code "121") (name "unconnected-(U1-NC.-Pad1)") (class "Default")
      (node (ref "U1") (pin "1") (pinfunction "NC._1") (pintype "passive"))
    )
  )
)
